# M8Breakout4.net
KiCad netlist of a schematic drawn in EAGLE
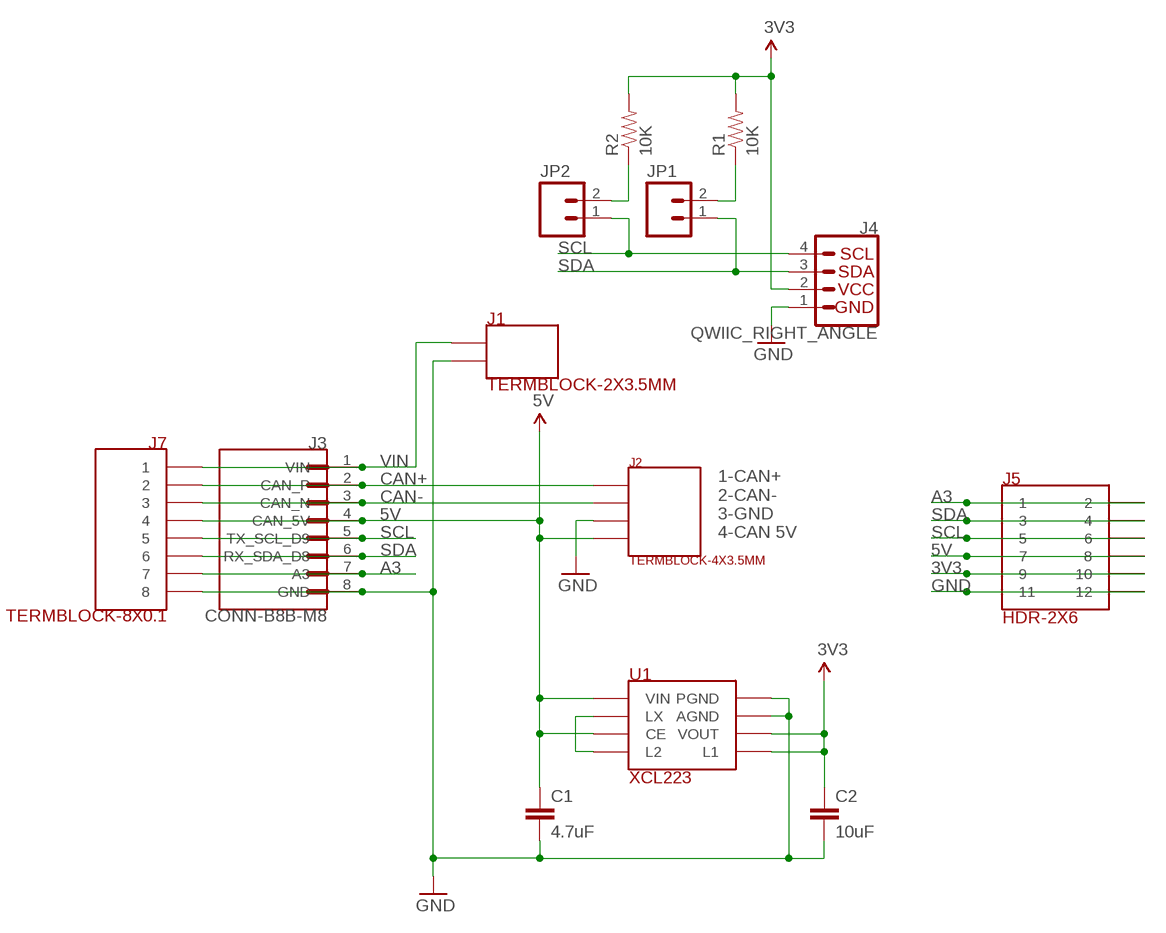
[diagram p0: schematic, sheet 1]

(export (version "E")
  (design (tool "Eeschema 10.0.6"))
  (components
    (comp (ref "C1")
      (value "4.7uF")
      (footprint "eagle-import:0603-CAP")
      (libsource (lib "eagle-import") (part "CAP-4.7UF-0603"))
    )
    (comp (ref "C2")
      (value "10uF")
      (footprint "eagle-import:0603-CAP")
      (libsource (lib "eagle-import") (part "CAP-10UF-0603"))
    )
    (comp (ref "J1")
      (value "TERMBLOCK-2X3.5MM")
      (footprint "eagle-import:TERMBLOCK-2X3.5MM")
      (libsource (lib "eagle-import") (part "TERMBLOCK-2X3.5MM"))
    )
    (comp (ref "J2")
      (value "TERMBLOCK-4X3.5MM")
      (footprint "eagle-import:TERMBLOCK-4X3.5MM")
      (libsource (lib "eagle-import") (part "TERMBLOCK-4X3.5MM"))
    )
    (comp (ref "J3")
      (value "CONN-B8B-M8")
      (footprint "eagle-import:JST_B8B-PH-SM4-TB(LF)(SN)")
      (libsource (lib "eagle-import") (part "CONN-B8B-M8"))
    )
    (comp (ref "J4")
      (value "QWIIC_RIGHT_ANGLE")
      (footprint "eagle-import:JST04_1MM_RA")
      (libsource (lib "eagle-import") (part "QWIIC_CONNECTORJS-1MM"))
    )
    (comp (ref "J5")
      (value "HDR-2X6")
      (footprint "eagle-import:HDR-2X6-F-SMD-NO-HOLES")
      (libsource (lib "eagle-import") (part "HDR-2X6"))
    )
    (comp (ref "J7")
      (value "TERMBLOCK-8X0.1")
      (footprint "eagle-import:TERMBLOCK-8X0.1")
      (libsource (lib "eagle-import") (part "TERMBLOCK-8X0.1"))
    )
    (comp (ref "JP1")
      (value "M02PTH")
      (footprint "eagle-import:1X02")
      (libsource (lib "eagle-import") (part "M02PTH"))
    )
    (comp (ref "JP2")
      (value "M02PTH")
      (footprint "eagle-import:1X02")
      (libsource (lib "eagle-import") (part "M02PTH"))
    )
    (comp (ref "R1")
      (value "10K")
      (footprint "eagle-import:0603-RES")
      (libsource (lib "eagle-import") (part "RES-10K-06030603"))
    )
    (comp (ref "R2")
      (value "10K")
      (footprint "eagle-import:0603-RES")
      (libsource (lib "eagle-import") (part "RES-10K-06030603"))
    )
    (comp (ref "U1")
      (value "XCL223")
      (footprint "eagle-import:REG-XCL223-LESS-CREAM")
      (libsource (lib "eagle-import") (part "REG-XCL223"))
    )
  )
  (nets
    (net (code "1") (name "/A3") (class "Default")
      (node (ref "J3") (pin "7") (pinfunction "A3_7") (pintype "passive"))
      (node (ref "J5") (pin "1") (pinfunction "1_1") (pintype "passive"))
      (node (ref "J5") (pin "2") (pinfunction "2_2") (pintype "passive"))
      (node (ref "J7") (pin "P$7") (pinfunction "7_P$7") (pintype "passive"))
    )
    (net (code "2") (name "/CAN+") (class "Default")
      (node (ref "J2") (pin "1") (pinfunction "1_1") (pintype "passive"))
      (node (ref "J3") (pin "2") (pinfunction "CAN_P_2") (pintype "passive"))
      (node (ref "J7") (pin "P$2") (pinfunction "2_P$2") (pintype "passive"))
    )
    (net (code "3") (name "/CAN-") (class "Default")
      (node (ref "J2") (pin "2") (pinfunction "2_2") (pintype "passive"))
      (node (ref "J3") (pin "3") (pinfunction "CAN_N_3") (pintype "passive"))
      (node (ref "J7") (pin "P$3") (pinfunction "3_P$3") (pintype "passive"))
    )
    (net (code "4") (name "/SCL") (class "Default")
      (node (ref "J3") (pin "5") (pinfunction "TX_SCL_D9_5") (pintype "passive"))
      (node (ref "J4") (pin "4") (pinfunction "4_4") (pintype "passive"))
      (node (ref "J5") (pin "5") (pinfunction "5_5") (pintype "passive"))
      (node (ref "J5") (pin "6") (pinfunction "6_6") (pintype "passive"))
      (node (ref "J7") (pin "P$5") (pinfunction "5_P$5") (pintype "passive"))
      (node (ref "JP2") (pin "1") (pinfunction "1_1") (pintype "passive"))
    )
    (net (code "5") (name "/SDA") (class "Default")
      (node (ref "J3") (pin "6") (pinfunction "RX_SDA_D8_6") (pintype "passive"))
      (node (ref "J4") (pin "3") (pinfunction "3_3") (pintype "passive"))
      (node (ref "J5") (pin "3") (pinfunction "3_3") (pintype "passive"))
      (node (ref "J5") (pin "4") (pinfunction "4_4") (pintype "passive"))
      (node (ref "J7") (pin "P$6") (pinfunction "6_P$6") (pintype "passive"))
      (node (ref "JP1") (pin "1") (pinfunction "1_1") (pintype "passive"))
    )
    (net (code "6") (name "/VIN") (class "Default")
      (node (ref "J1") (pin "1") (pinfunction "1_1") (pintype "passive"))
      (node (ref "J3") (pin "1") (pinfunction "VIN_1") (pintype "passive"))
      (node (ref "J7") (pin "P$1") (pinfunction "1_P$1") (pintype "passive"))
    )
    (net (code "7") (name "3V3") (class "Default")
      (node (ref "C2") (pin "1") (pinfunction "1_1") (pintype "passive"))
      (node (ref "J4") (pin "2") (pinfunction "2_2") (pintype "power_in"))
      (node (ref "J5") (pin "10") (pinfunction "10_10") (pintype "passive"))
      (node (ref "J5") (pin "9") (pinfunction "9_9") (pintype "passive"))
      (node (ref "R1") (pin "2") (pinfunction "2_2") (pintype "passive"))
      (node (ref "R2") (pin "2") (pinfunction "2_2") (pintype "passive"))
      (node (ref "U1") (pin "3") (pinfunction "VOUT_3") (pintype "passive"))
      (node (ref "U1") (pin "7") (pinfunction "L1_7") (pintype "passive"))
    )
    (net (code "8") (name "5V") (class "Default")
      (node (ref "C1") (pin "1") (pinfunction "1_1") (pintype "passive"))
      (node (ref "J2") (pin "4") (pinfunction "4_4") (pintype "passive"))
      (node (ref "J3") (pin "4") (pinfunction "CAN_5V_4") (pintype "passive"))
      (node (ref "J5") (pin "7") (pinfunction "7_7") (pintype "passive"))
      (node (ref "J5") (pin "8") (pinfunction "8_8") (pintype "passive"))
      (node (ref "J7") (pin "P$4") (pinfunction "4_P$4") (pintype "passive"))
      (node (ref "U1") (pin "4") (pinfunction "CE_4") (pintype "input"))
      (node (ref "U1") (pin "6") (pinfunction "VIN_6") (pintype "power_in"))
    )
    (net (code "9") (name "GND") (class "Default")
      (node (ref "C1") (pin "2") (pinfunction "2_2") (pintype "passive"))
      (node (ref "C2") (pin "2") (pinfunction "2_2") (pintype "passive"))
      (node (ref "J1") (pin "2") (pinfunction "2_2") (pintype "passive"))
      (node (ref "J2") (pin "3") (pinfunction "3_3") (pintype "passive"))
      (node (ref "J3") (pin "8") (pinfunction "GND_8") (pintype "passive"))
      (node (ref "J4") (pin "1") (pinfunction "1_1") (pintype "power_in"))
      (node (ref "J5") (pin "11") (pinfunction "11_11") (pintype "passive"))
      (node (ref "J5") (pin "12") (pinfunction "12_12") (pintype "passive"))
      (node (ref "J7") (pin "P$8") (pinfunction "8_P$8") (pintype "passive"))
      (node (ref "U1") (pin "1") (pinfunction "PGND_1") (pintype "passive"))
      (node (ref "U1") (pin "2") (pinfunction "AGND_2") (pintype "passive"))
    )
    (net (code "10") (name "Net-(JP1-Pad2)") (class "Default")
      (node (ref "JP1") (pin "2") (pinfunction "2_2") (pintype "passive"))
      (node (ref "R1") (pin "1") (pinfunction "1_1") (pintype "passive"))
    )
    (net (code "11") (name "Net-(JP2-Pad2)") (class "Default")
      (node (ref "JP2") (pin "2") (pinfunction "2_2") (pintype "passive"))
      (node (ref "R2") (pin "1") (pinfunction "1_1") (pintype "passive"))
    )
    (net (code "12") (name "Net-(U1-L2)") (class "Default")
      (node (ref "U1") (pin "5") (pinfunction "LX_5") (pintype "passive"))
      (node (ref "U1") (pin "8") (pinfunction "L2_8") (pintype "passive"))
    )
  )
)
